# SW_DIP8_SMT.net
KiCad netlist of a schematic drawn in Altium Designer
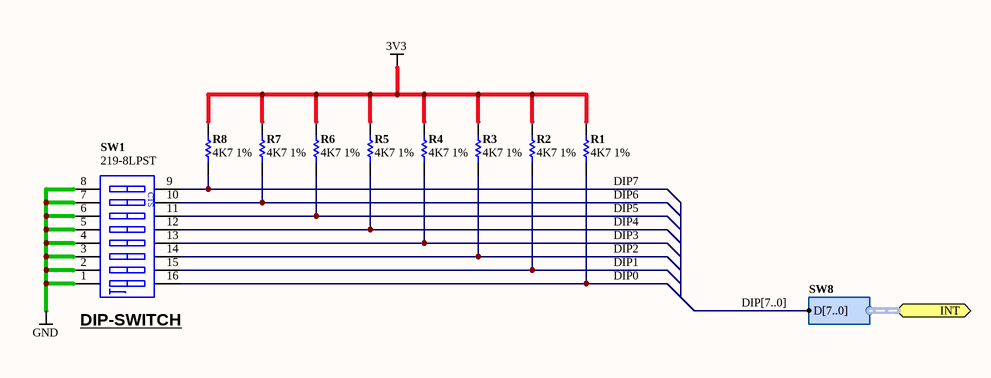
[diagram p0: SW_DIP8_SMT.SchDoc]

(export (version "E")
  (design (tool "Eeschema 10.0.6"))
  (components
    (comp (ref "R1")
      (value "4K7 1%")
      (footprint "RESC1005-STAR")
      (description "Resistor, 4K7 1% 0402 (1005)")
      (fields (field (name "TOLERANCE") "1 %"))
      (libsource (lib "altium-import") (part "root_2_RES_"))
    )
    (comp (ref "R2")
      (value "4K7 1%")
      (footprint "RESC1005-STAR")
      (description "Resistor, 4K7 1% 0402 (1005)")
      (fields (field (name "TOLERANCE") "1 %"))
      (libsource (lib "altium-import") (part "root_2_RES_"))
    )
    (comp (ref "R3")
      (value "4K7 1%")
      (footprint "RESC1005-STAR")
      (description "Resistor, 4K7 1% 0402 (1005)")
      (fields (field (name "TOLERANCE") "1 %"))
      (libsource (lib "altium-import") (part "root_2_RES_"))
    )
    (comp (ref "R4")
      (value "4K7 1%")
      (footprint "RESC1005-STAR")
      (description "Resistor, 4K7 1% 0402 (1005)")
      (fields (field (name "TOLERANCE") "1 %"))
      (libsource (lib "altium-import") (part "root_2_RES_"))
    )
    (comp (ref "R5")
      (value "4K7 1%")
      (footprint "RESC1005-STAR")
      (description "Resistor, 4K7 1% 0402 (1005)")
      (fields (field (name "TOLERANCE") "1 %"))
      (libsource (lib "altium-import") (part "root_2_RES_"))
    )
    (comp (ref "R6")
      (value "4K7 1%")
      (footprint "RESC1005-STAR")
      (description "Resistor, 4K7 1% 0402 (1005)")
      (fields (field (name "TOLERANCE") "1 %"))
      (libsource (lib "altium-import") (part "root_2_RES_"))
    )
    (comp (ref "R7")
      (value "4K7 1%")
      (footprint "RESC1005-STAR")
      (description "Resistor, 4K7 1% 0402 (1005)")
      (fields (field (name "TOLERANCE") "1 %"))
      (libsource (lib "altium-import") (part "root_2_RES_"))
    )
    (comp (ref "R8")
      (value "4K7 1%")
      (footprint "RESC1005-STAR")
      (description "Resistor, 4K7 1% 0402 (1005)")
      (fields (field (name "TOLERANCE") "1 %"))
      (libsource (lib "altium-import") (part "root_2_RES_"))
    )
    (comp (ref "SW1")
      (value "219-8LPST")
      (footprint "219-8LPST")
      (description "Switch, SPST, Surface Mount DIP, 8-way")
      (libsource (lib "AltiumDesignLibrary") (part "219-8LPST-8"))
    )
  )
  (nets
    (net (code "2") (name "/DIP0") (class "Default")
      (node (ref "R1") (pin "1") (pinfunction "1_1") (pintype "passive"))
      (node (ref "SW1") (pin "16") (pinfunction "B1_16") (pintype "passive"))
    )
    (net (code "3") (name "/DIP1") (class "Default")
      (node (ref "R2") (pin "1") (pinfunction "1_1") (pintype "passive"))
      (node (ref "SW1") (pin "15") (pinfunction "B2_15") (pintype "passive"))
    )
    (net (code "4") (name "/DIP2") (class "Default")
      (node (ref "R3") (pin "1") (pinfunction "1_1") (pintype "passive"))
      (node (ref "SW1") (pin "14") (pinfunction "B3_14") (pintype "passive"))
    )
    (net (code "5") (name "/DIP3") (class "Default")
      (node (ref "R4") (pin "1") (pinfunction "1_1") (pintype "passive"))
      (node (ref "SW1") (pin "13") (pinfunction "B4_13") (pintype "passive"))
    )
    (net (code "6") (name "/DIP4") (class "Default")
      (node (ref "R5") (pin "1") (pinfunction "1_1") (pintype "passive"))
      (node (ref "SW1") (pin "12") (pinfunction "B5_12") (pintype "passive"))
    )
    (net (code "7") (name "/DIP5") (class "Default")
      (node (ref "R6") (pin "1") (pinfunction "1_1") (pintype "passive"))
      (node (ref "SW1") (pin "11") (pinfunction "B6_11") (pintype "passive"))
    )
    (net (code "8") (name "/DIP6") (class "Default")
      (node (ref "R7") (pin "1") (pinfunction "1_1") (pintype "passive"))
      (node (ref "SW1") (pin "10") (pinfunction "B7_10") (pintype "passive"))
    )
    (net (code "9") (name "/DIP7") (class "Default")
      (node (ref "R8") (pin "1") (pinfunction "1_1") (pintype "passive"))
      (node (ref "SW1") (pin "9") (pinfunction "B8_9") (pintype "passive"))
    )
    (net (code "12") (name "3V3") (class "Default")
      (node (ref "R1") (pin "2") (pinfunction "2_2") (pintype "passive"))
      (node (ref "R2") (pin "2") (pinfunction "2_2") (pintype "passive"))
      (node (ref "R3") (pin "2") (pinfunction "2_2") (pintype "passive"))
      (node (ref "R4") (pin "2") (pinfunction "2_2") (pintype "passive"))
      (node (ref "R5") (pin "2") (pinfunction "2_2") (pintype "passive"))
      (node (ref "R6") (pin "2") (pinfunction "2_2") (pintype "passive"))
      (node (ref "R7") (pin "2") (pinfunction "2_2") (pintype "passive"))
      (node (ref "R8") (pin "2") (pinfunction "2_2") (pintype "passive"))
    )
    (net (code "13") (name "GND") (class "Default")
      (node (ref "SW1") (pin "1") (pinfunction "A1_1") (pintype "passive"))
      (node (ref "SW1") (pin "2") (pinfunction "A2_2") (pintype "passive"))
      (node (ref "SW1") (pin "3") (pinfunction "A3_3") (pintype "passive"))
      (node (ref "SW1") (pin "4") (pinfunction "A4_4") (pintype "passive"))
      (node (ref "SW1") (pin "5") (pinfunction "A5_5") (pintype "passive"))
      (node (ref "SW1") (pin "6") (pinfunction "A6_6") (pintype "passive"))
      (node (ref "SW1") (pin "7") (pinfunction "A7_7") (pintype "passive"))
      (node (ref "SW1") (pin "8") (pinfunction "A8_8") (pintype "passive"))
    )
  )
)
